# OpenBook_v13.net
KiCad netlist of a schematic drawn in EAGLE
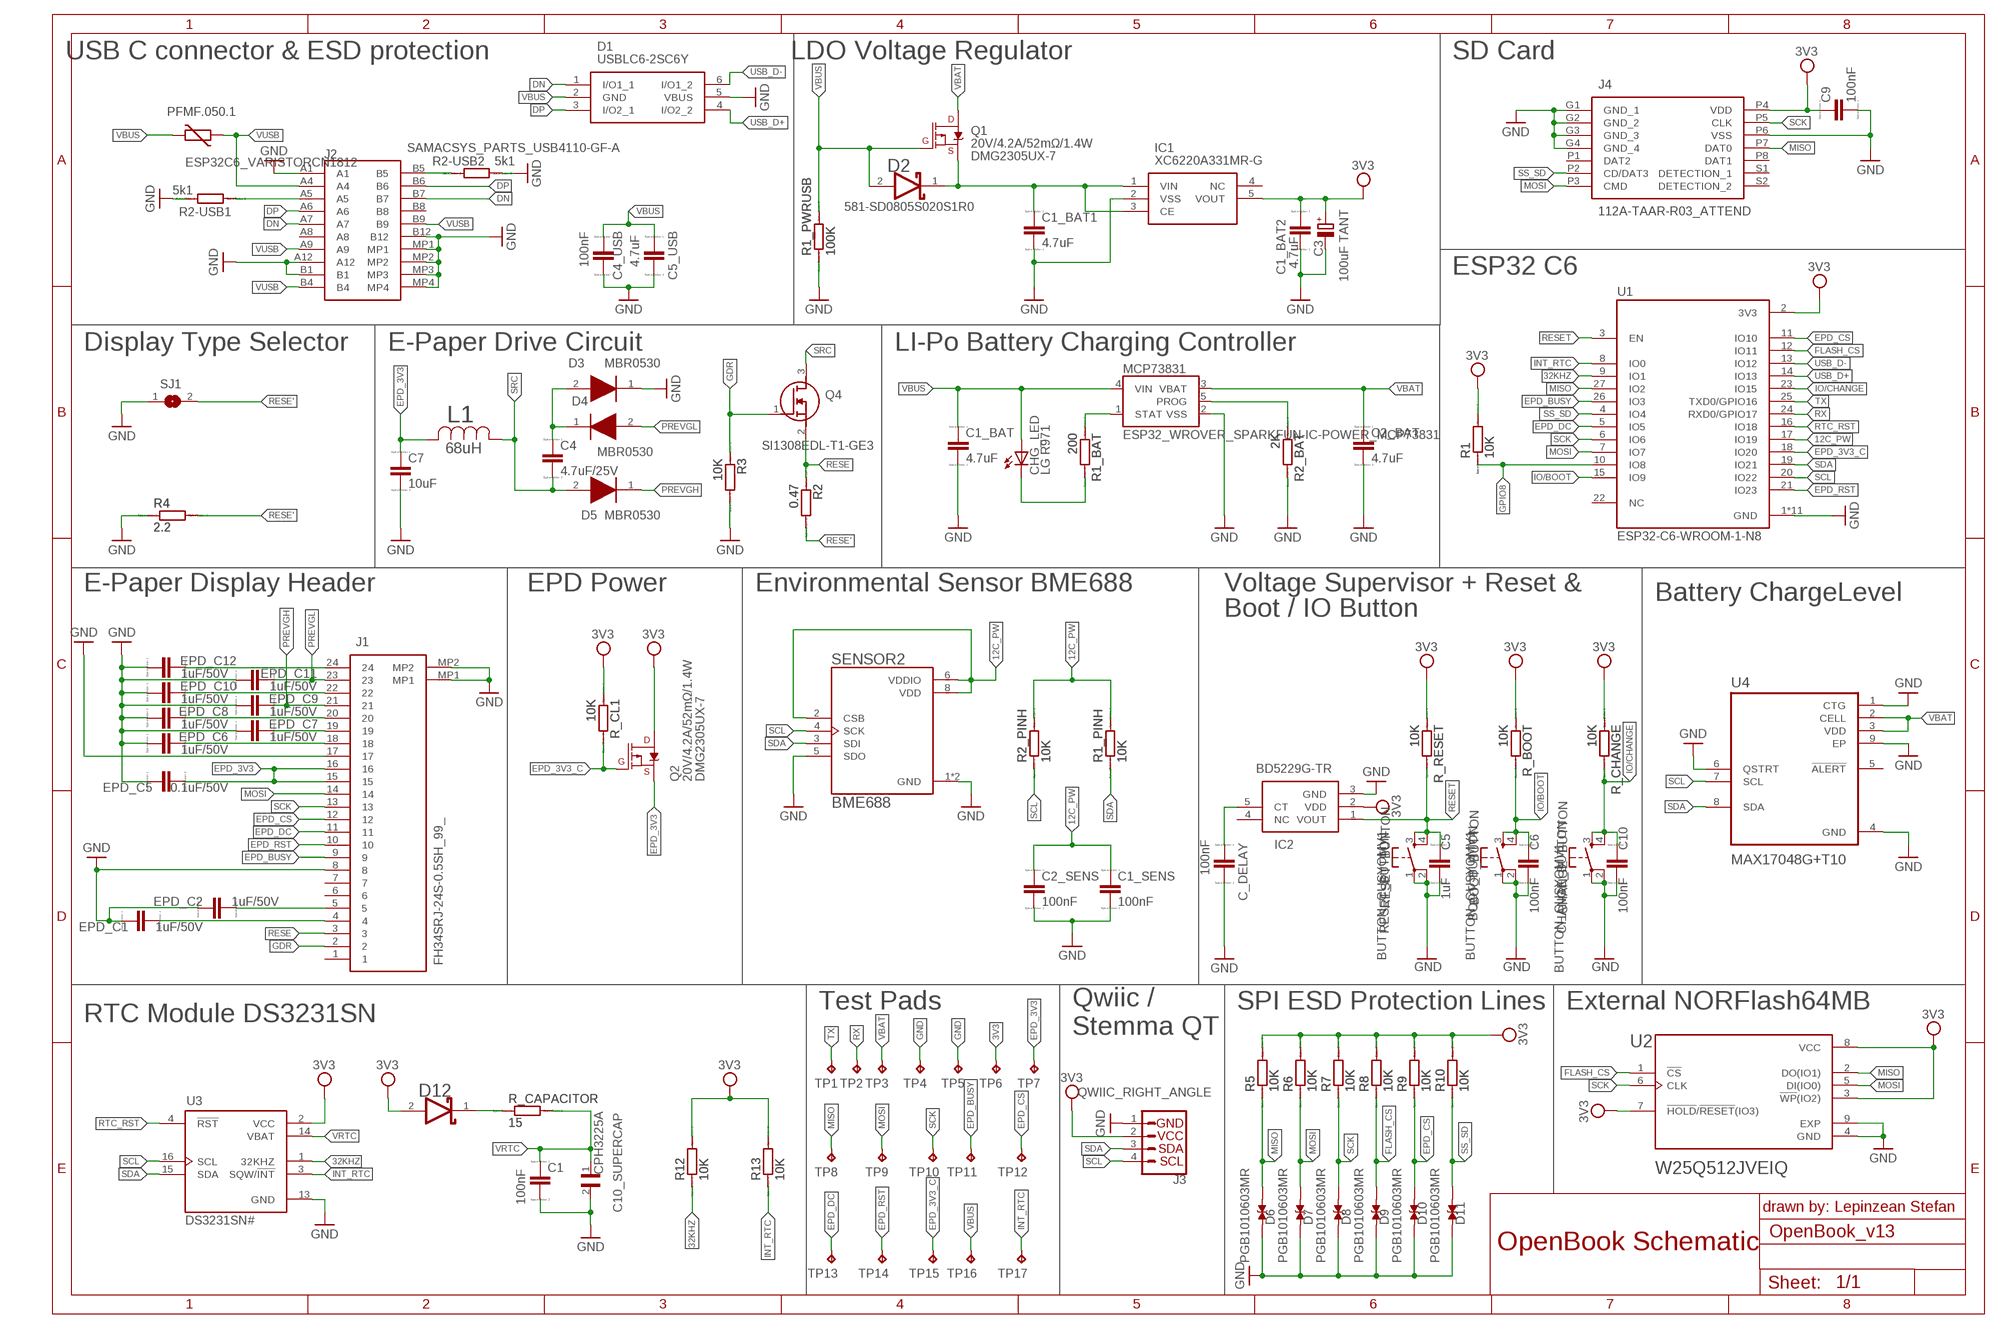
[diagram p0: schematic, sheet 1]

(export (version "E")
  (design (tool "Eeschema 10.0.6"))
  (components
    (comp (ref "BOOT_BUTTON")
      (value "BUTTON_CUSYOMV1")
      (footprint "eagle-import:MYBUTTON")
      (libsource (lib "eagle-import") (part "BUTTON_CUSYOMV1"))
    )
    (comp (ref "C1")
      (value "100nF")
      (footprint "eagle-import:EAGLE-LTSPICE_C0402")
      (libsource (lib "eagle-import") (part "EAGLE-LTSPICE_CC0402"))
    )
    (comp (ref "C1_BAT")
      (value "4.7uF")
      (footprint "eagle-import:EAGLE-LTSPICE_C0402")
      (libsource (lib "eagle-import") (part "EAGLE-LTSPICE_CC0402"))
    )
    (comp (ref "C1_BAT1")
      (value "4.7uF")
      (footprint "eagle-import:EAGLE-LTSPICE_C0402")
      (libsource (lib "eagle-import") (part "EAGLE-LTSPICE_CC0402"))
    )
    (comp (ref "C1_BAT2")
      (value "4.7uF")
      (footprint "eagle-import:EAGLE-LTSPICE_C0402")
      (libsource (lib "eagle-import") (part "EAGLE-LTSPICE_CC0402"))
    )
    (comp (ref "C1_SENS")
      (value "100nF")
      (footprint "eagle-import:EAGLE-LTSPICE_C0402")
      (libsource (lib "eagle-import") (part "EAGLE-LTSPICE_CC0402"))
    )
    (comp (ref "C2_BAT")
      (value "4.7uF")
      (footprint "eagle-import:EAGLE-LTSPICE_C0402")
      (libsource (lib "eagle-import") (part "EAGLE-LTSPICE_CC0402"))
    )
    (comp (ref "C2_SENS")
      (value "100nF")
      (footprint "eagle-import:EAGLE-LTSPICE_C0402")
      (libsource (lib "eagle-import") (part "EAGLE-LTSPICE_CC0402"))
    )
    (comp (ref "C3")
      (value "100uF TANT")
      (footprint "eagle-import:RCL_CT3528")
      (libsource (lib "eagle-import") (part "RCL_CPOL-EUCT3528"))
    )
    (comp (ref "C4")
      (value "4.7uF/25V")
      (footprint "eagle-import:EAGLE-LTSPICE_C0402")
      (libsource (lib "eagle-import") (part "EAGLE-LTSPICE_CC0402"))
    )
    (comp (ref "C4_USB")
      (value "100nF")
      (footprint "eagle-import:EAGLE-LTSPICE_C0402")
      (libsource (lib "eagle-import") (part "EAGLE-LTSPICE_CC0402"))
    )
    (comp (ref "C5")
      (value "1uF")
      (footprint "eagle-import:EAGLE-LTSPICE_C0402")
      (libsource (lib "eagle-import") (part "EAGLE-LTSPICE_CC0402"))
    )
    (comp (ref "C5_USB")
      (value "4.7uF")
      (footprint "eagle-import:EAGLE-LTSPICE_C0402")
      (libsource (lib "eagle-import") (part "EAGLE-LTSPICE_CC0402"))
    )
    (comp (ref "C6")
      (value "100nF")
      (footprint "eagle-import:EAGLE-LTSPICE_C0402")
      (libsource (lib "eagle-import") (part "EAGLE-LTSPICE_CC0402"))
    )
    (comp (ref "C7")
      (value "10uF")
      (footprint "eagle-import:EAGLE-LTSPICE_C0402")
      (libsource (lib "eagle-import") (part "EAGLE-LTSPICE_CC0402"))
    )
    (comp (ref "C9")
      (value "100nF")
      (footprint "eagle-import:EAGLE-LTSPICE_C0402")
      (libsource (lib "eagle-import") (part "EAGLE-LTSPICE_CC0402"))
    )
    (comp (ref "C10")
      (value "100nF")
      (footprint "eagle-import:EAGLE-LTSPICE_C0402")
      (libsource (lib "eagle-import") (part "EAGLE-LTSPICE_CC0402"))
    )
    (comp (ref "C10_SUPERCAP")
      (value "CPH3225A")
      (footprint "eagle-import:CAPCP3225X100N")
      (fields (field (name "MF") "Seiko Instruments"))
      (libsource (lib "eagle-import") (part "CPH3225A"))
    )
    (comp (ref "CHANGE_BUTTON")
      (value "BUTTON_CUSYOMV1")
      (footprint "eagle-import:MYBUTTON")
      (libsource (lib "eagle-import") (part "BUTTON_CUSYOMV1"))
    )
    (comp (ref "CHG_LED")
      (value "LG R971")
      (footprint "eagle-import:ADAFRUIT_CHIP-LED0603")
      (libsource (lib "eagle-import") (part "ADAFRUIT_LEDCHIP-LED0603"))
    )
    (comp (ref "C_DELAY")
      (value "100nF")
      (footprint "eagle-import:EAGLE-LTSPICE_C0402")
      (libsource (lib "eagle-import") (part "EAGLE-LTSPICE_CC0402"))
    )
    (comp (ref "D1")
      (value "USBLC6-2SC6Y")
      (footprint "eagle-import:SOT95P280X145-6N")
      (fields (field (name "MF") "STMicroelectronics"))
      (libsource (lib "eagle-import") (part "USBLC6-2SC6Y"))
    )
    (comp (ref "D2")
      (value "ESP32_WROVER_AVX---SD0805S020S1R0_AVX_SD0805S020S1R0_0_0AVX_SD0805S020S1R0_0_0")
      (footprint "eagle-import:ESP32_WROVER_AVX---SD0805S020S1R0_AVX_SD0805S020S1R0_0")
      (fields
        (field (name "DIGIKEY_PART_NUMBER") "478-7800-1-ND")
        (field (name "MF") "AVX")
        (field (name "MOUSER_PART_NUMBER") "581-SD0805S020S1R0")
      )
      (libsource (lib "eagle-import") (part "ESP32_WROVER_AVX---SD0805S020S1R0_AVX_SD0805S020S1R0_0_0AVX_SD0805S020S1R0_0_0"))
    )
    (comp (ref "D3")
      (value "MBR0530")
      (footprint "eagle-import:SOD3716X135N")
      (fields (field (name "MF") "ON Semiconductor"))
      (libsource (lib "eagle-import") (part "MBR0530"))
    )
    (comp (ref "D4")
      (value "MBR0530")
      (footprint "eagle-import:SOD3716X135N")
      (fields (field (name "MF") "ON Semiconductor"))
      (libsource (lib "eagle-import") (part "MBR0530"))
    )
    (comp (ref "D5")
      (value "MBR0530")
      (footprint "eagle-import:SOD3716X135N")
      (fields (field (name "MF") "ON Semiconductor"))
      (libsource (lib "eagle-import") (part "MBR0530"))
    )
    (comp (ref "D6")
      (value "PGB1010603MR")
      (footprint "eagle-import:DIOC1608X36N")
      (fields (field (name "MF") "Littelfuse Inc."))
      (libsource (lib "eagle-import") (part "PGB1010603MR"))
    )
    (comp (ref "D7")
      (value "PGB1010603MR")
      (footprint "eagle-import:DIOC1608X36N")
      (fields (field (name "MF") "Littelfuse Inc."))
      (libsource (lib "eagle-import") (part "PGB1010603MR"))
    )
    (comp (ref "D8")
      (value "PGB1010603MR")
      (footprint "eagle-import:DIOC1608X36N")
      (fields (field (name "MF") "Littelfuse Inc."))
      (libsource (lib "eagle-import") (part "PGB1010603MR"))
    )
    (comp (ref "D9")
      (value "PGB1010603MR")
      (footprint "eagle-import:DIOC1608X36N")
      (fields (field (name "MF") "Littelfuse Inc."))
      (libsource (lib "eagle-import") (part "PGB1010603MR"))
    )
    (comp (ref "D10")
      (value "PGB1010603MR")
      (footprint "eagle-import:DIOC1608X36N")
      (fields (field (name "MF") "Littelfuse Inc."))
      (libsource (lib "eagle-import") (part "PGB1010603MR"))
    )
    (comp (ref "D11")
      (value "PGB1010603MR")
      (footprint "eagle-import:DIOC1608X36N")
      (fields (field (name "MF") "Littelfuse Inc."))
      (libsource (lib "eagle-import") (part "PGB1010603MR"))
    )
    (comp (ref "D12")
      (value "ESP32_WROVER_AVX---SD0805S020S1R0_AVX_SD0805S020S1R0_0_0AVX_SD0805S020S1R0_0_0")
      (footprint "eagle-import:ESP32_WROVER_AVX---SD0805S020S1R0_AVX_SD0805S020S1R0_0")
      (fields
        (field (name "DIGIKEY_PART_NUMBER") "478-7800-1-ND")
        (field (name "MF") "AVX")
        (field (name "MOUSER_PART_NUMBER") "581-SD0805S020S1R0")
      )
      (libsource (lib "eagle-import") (part "ESP32_WROVER_AVX---SD0805S020S1R0_AVX_SD0805S020S1R0_0_0AVX_SD0805S020S1R0_0_0"))
    )
    (comp (ref "EPD_C1")
      (value "1uF/50V")
      (footprint "eagle-import:EAGLE-LTSPICE_C0402")
      (libsource (lib "eagle-import") (part "EAGLE-LTSPICE_CC0402"))
    )
    (comp (ref "EPD_C2")
      (value "1uF/50V")
      (footprint "eagle-import:EAGLE-LTSPICE_C0402")
      (libsource (lib "eagle-import") (part "EAGLE-LTSPICE_CC0402"))
    )
    (comp (ref "EPD_C5")
      (value "0.1uF/50V")
      (footprint "eagle-import:EAGLE-LTSPICE_C0402")
      (libsource (lib "eagle-import") (part "EAGLE-LTSPICE_CC0402"))
    )
    (comp (ref "EPD_C6")
      (value "1uF/50V")
      (footprint "eagle-import:EAGLE-LTSPICE_C0402")
      (libsource (lib "eagle-import") (part "EAGLE-LTSPICE_CC0402"))
    )
    (comp (ref "EPD_C7")
      (value "1uF/50V")
      (footprint "eagle-import:EAGLE-LTSPICE_C0402")
      (libsource (lib "eagle-import") (part "EAGLE-LTSPICE_CC0402"))
    )
    (comp (ref "EPD_C8")
      (value "1uF/50V")
      (footprint "eagle-import:EAGLE-LTSPICE_C0402")
      (libsource (lib "eagle-import") (part "EAGLE-LTSPICE_CC0402"))
    )
    (comp (ref "EPD_C9")
      (value "1uF/50V")
      (footprint "eagle-import:EAGLE-LTSPICE_C0402")
      (libsource (lib "eagle-import") (part "EAGLE-LTSPICE_CC0402"))
    )
    (comp (ref "EPD_C10")
      (value "1uF/50V")
      (footprint "eagle-import:EAGLE-LTSPICE_C0402")
      (libsource (lib "eagle-import") (part "EAGLE-LTSPICE_CC0402"))
    )
    (comp (ref "EPD_C11")
      (value "1uF/50V")
      (footprint "eagle-import:EAGLE-LTSPICE_C0402")
      (libsource (lib "eagle-import") (part "EAGLE-LTSPICE_CC0402"))
    )
    (comp (ref "EPD_C12")
      (value "1uF/50V")
      (footprint "eagle-import:EAGLE-LTSPICE_C0402")
      (libsource (lib "eagle-import") (part "EAGLE-LTSPICE_CC0402"))
    )
    (comp (ref "IC1")
      (value "XC6220A331MR-G")
      (footprint "eagle-import:SOT95P280X120-5N")
      (fields (field (name "MOUSER_PART_NUMBER") "865-XC6220A331MR-G"))
      (libsource (lib "eagle-import") (part "XC6220A331MR-G"))
    )
    (comp (ref "IC2")
      (value "BD5229G-TR")
      (footprint "eagle-import:SOT95P280X125-5N")
      (fields (field (name "MOUSER_PART_NUMBER") "755-BD5229G-TR"))
      (libsource (lib "eagle-import") (part "BD5229G-TR"))
    )
    (comp (ref "J1")
      (value "FH34SRJ-24S-0.5SH_99_")
      (footprint "eagle-import:FH34SRJ24S05SH99")
      (fields
        (field (name "MANUFACTURER_PART_NUMBER") "FH34SRJ-24S-0.5SH(99)")
        (field (name "MOUSER_PART_NUMBER") "798-FH34SRJ24S05SH99")
      )
      (libsource (lib "eagle-import") (part "FH34SRJ-24S-0.5SH_99_"))
    )
    (comp (ref "J2")
      (value "SAMACSYS_PARTS_USB4110-GF-A")
      (footprint "eagle-import:SAMACSYS_PARTS_USB4110GFA")
      (fields
        (field (name "MANUFACTURER_PART_NUMBER") "USB4110-GF-A")
        (field (name "MOUSER_PART_NUMBER") "640-USB4110-GF-A")
      )
      (libsource (lib "eagle-import") (part "SAMACSYS_PARTS_USB4110-GF-A"))
    )
    (comp (ref "J3")
      (value "QWIIC_RIGHT_ANGLE")
      (footprint "eagle-import:JST04_1MM_RA")
      (libsource (lib "eagle-import") (part "QWIIC_CONNECTORJS-1MM"))
    )
    (comp (ref "J4")
      (value "112A-TAAR-R03_ATTEND")
      (footprint "eagle-import:112ATAARR03ATTEND")
      (fields (field (name "MANUFACTURER_PART_NUMBER") "112A-TAAR-R03 ATTEND"))
      (libsource (lib "eagle-import") (part "112A-TAAR-R03_ATTEND"))
    )
    (comp (ref "L1")
      (value "68uH")
      (footprint "eagle-import:IND_4828-WE-TPC_WRE")
      (fields
        (field (name "MANUFACTURER_PART_NUMBER") "744043680")
        (field (name "COPYRIGHT") "Copyright (C) 2024 Ultra Librarian. All rights reserved.")
      )
      (libsource (lib "eagle-import") (part "744043680IND_4828-WE-TPC_WRE"))
    )
    (comp (ref "MCP73831")
      (value "ESP32_WROVER_SPARKFUN-IC-POWER_MCP73831")
      (footprint "eagle-import:ESP32_WROVER_SPARKFUN-IC-POWER_SOT23-5")
      (libsource (lib "eagle-import") (part "ESP32_WROVER_SPARKFUN-IC-POWER_MCP73831"))
    )
    (comp (ref "PFMF.050.1")
      (value "ESP32C6_VARISTORCN1812")
      (footprint "eagle-import:ESP32C6_VARISTOR_CT_CN1812")
      (libsource (lib "eagle-import") (part "ESP32C6_VARISTORCN1812"))
    )
    (comp (ref "Q1")
      (value "20V/4.2A/52mΩ/1.4W")
      (footprint "eagle-import:ESP32_WROVER_SPARKFUN-DISCRETESEMI_SOT23-3")
      (fields (field (name "PROD_ID") "DMG2305UX-7"))
      (libsource (lib "eagle-import") (part "ESP32_WROVER_SPARKFUN-DISCRETESEMI_MOSFET_PCH-DMG2305UX-7"))
    )
    (comp (ref "Q2")
      (value "20V/4.2A/52mΩ/1.4W")
      (footprint "eagle-import:ESP32_WROVER_SPARKFUN-DISCRETESEMI_SOT23-3")
      (fields (field (name "PROD_ID") "DMG2305UX-7"))
      (libsource (lib "eagle-import") (part "ESP32_WROVER_SPARKFUN-DISCRETESEMI_MOSFET_PCH-DMG2305UX-7"))
    )
    (comp (ref "Q4")
      (value "SI1308EDL-T1-GE3")
      (footprint "eagle-import:SOT65P210X110-3N")
      (fields (field (name "MF") "Vishay Siliconix"))
      (libsource (lib "eagle-import") (part "SI1308EDL-T1-GE3"))
    )
    (comp (ref "R1")
      (value "10K")
      (footprint "eagle-import:R0402")
      (libsource (lib "eagle-import") (part "ESP32_WROVER_EAGLE-LTSPICE_RR0402"))
    )
    (comp (ref "R1_BAT")
      (value "200")
      (footprint "eagle-import:R0402")
      (libsource (lib "eagle-import") (part "ESP32_WROVER_EAGLE-LTSPICE_RR0402"))
    )
    (comp (ref "R1_PINH")
      (value "10K")
      (footprint "eagle-import:R0402")
      (libsource (lib "eagle-import") (part "ESP32_WROVER_EAGLE-LTSPICE_RR0402"))
    )
    (comp (ref "R1_PWRUSB")
      (value "100K")
      (footprint "eagle-import:R0402")
      (libsource (lib "eagle-import") (part "ESP32_WROVER_EAGLE-LTSPICE_RR0402"))
    )
    (comp (ref "R2")
      (value "0.47")
      (footprint "eagle-import:R0402")
      (libsource (lib "eagle-import") (part "ESP32_WROVER_EAGLE-LTSPICE_RR0402"))
    )
    (comp (ref "R2-USB1")
      (value "5k1")
      (footprint "eagle-import:R0402")
      (libsource (lib "eagle-import") (part "ESP32_WROVER_EAGLE-LTSPICE_RR0402"))
    )
    (comp (ref "R2-USB2")
      (value "5k1")
      (footprint "eagle-import:R0402")
      (libsource (lib "eagle-import") (part "ESP32_WROVER_EAGLE-LTSPICE_RR0402"))
    )
    (comp (ref "R2_BAT")
      (value "2K")
      (footprint "eagle-import:R0402")
      (libsource (lib "eagle-import") (part "ESP32_WROVER_EAGLE-LTSPICE_RR0402"))
    )
    (comp (ref "R2_PINH")
      (value "10K")
      (footprint "eagle-import:R0402")
      (libsource (lib "eagle-import") (part "ESP32_WROVER_EAGLE-LTSPICE_RR0402"))
    )
    (comp (ref "R3")
      (value "10K")
      (footprint "eagle-import:R0402")
      (libsource (lib "eagle-import") (part "ESP32_WROVER_EAGLE-LTSPICE_RR0402"))
    )
    (comp (ref "R4")
      (value "2.2")
      (footprint "eagle-import:R0402")
      (libsource (lib "eagle-import") (part "ESP32_WROVER_EAGLE-LTSPICE_RR0402"))
    )
    (comp (ref "R5")
      (value "10K")
      (footprint "eagle-import:R0402")
      (libsource (lib "eagle-import") (part "ESP32_WROVER_EAGLE-LTSPICE_RR0402"))
    )
    (comp (ref "R6")
      (value "10K")
      (footprint "eagle-import:R0402")
      (libsource (lib "eagle-import") (part "ESP32_WROVER_EAGLE-LTSPICE_RR0402"))
    )
    (comp (ref "R7")
      (value "10K")
      (footprint "eagle-import:R0402")
      (libsource (lib "eagle-import") (part "ESP32_WROVER_EAGLE-LTSPICE_RR0402"))
    )
    (comp (ref "R8")
      (value "10K")
      (footprint "eagle-import:R0402")
      (libsource (lib "eagle-import") (part "ESP32_WROVER_EAGLE-LTSPICE_RR0402"))
    )
    (comp (ref "R9")
      (value "10K")
      (footprint "eagle-import:R0402")
      (libsource (lib "eagle-import") (part "ESP32_WROVER_EAGLE-LTSPICE_RR0402"))
    )
    (comp (ref "R10")
      (value "10K")
      (footprint "eagle-import:R0402")
      (libsource (lib "eagle-import") (part "ESP32_WROVER_EAGLE-LTSPICE_RR0402"))
    )
    (comp (ref "R12")
      (value "10K")
      (footprint "eagle-import:R0402")
      (libsource (lib "eagle-import") (part "ESP32_WROVER_EAGLE-LTSPICE_RR0402"))
    )
    (comp (ref "R13")
      (value "10K")
      (footprint "eagle-import:R0402")
      (libsource (lib "eagle-import") (part "ESP32_WROVER_EAGLE-LTSPICE_RR0402"))
    )
    (comp (ref "RESET_BUTTON")
      (value "BUTTON_CUSYOMV1")
      (footprint "eagle-import:MYBUTTON")
      (libsource (lib "eagle-import") (part "BUTTON_CUSYOMV1"))
    )
    (comp (ref "R_BOOT")
      (value "10K")
      (footprint "eagle-import:R0402")
      (libsource (lib "eagle-import") (part "ESP32_WROVER_EAGLE-LTSPICE_RR0402"))
    )
    (comp (ref "R_CAPACITOR")
      (value "15")
      (footprint "eagle-import:R0402")
      (libsource (lib "eagle-import") (part "ESP32_WROVER_EAGLE-LTSPICE_RR0402"))
    )
    (comp (ref "R_CHANGE")
      (value "10K")
      (footprint "eagle-import:R0402")
      (libsource (lib "eagle-import") (part "ESP32_WROVER_EAGLE-LTSPICE_RR0402"))
    )
    (comp (ref "R_CL1")
      (value "10K")
      (footprint "eagle-import:R0402")
      (libsource (lib "eagle-import") (part "ESP32_WROVER_EAGLE-LTSPICE_RR0402"))
    )
    (comp (ref "R_RESET")
      (value "10K")
      (footprint "eagle-import:R0402")
      (libsource (lib "eagle-import") (part "ESP32_WROVER_EAGLE-LTSPICE_RR0402"))
    )
    (comp (ref "SENSOR2")
      (value "BME688")
      (footprint "eagle-import:ESP32_WROVER_BME680_PSON80P300X300X100-8N")
      (fields (field (name "MF") "Bosch Sensortec") (field (name "MP") "BME680"))
      (libsource (lib "eagle-import") (part "ESP32_WROVER_BME680_BME680"))
    )
    (comp (ref "SJ1") (value "SJ") (footprint "eagle-import:SJ") (libsource (lib "eagle-import") (part "SJ")))
    (comp (ref "TP1")
      (value "TPTP20R")
      (footprint "eagle-import:TP20R")
      (libsource (lib "eagle-import") (part "TPTP20R"))
    )
    (comp (ref "TP2")
      (value "TPTP20R")
      (footprint "eagle-import:TP20R")
      (libsource (lib "eagle-import") (part "TPTP20R"))
    )
    (comp (ref "TP3")
      (value "TPTP20R")
      (footprint "eagle-import:TP20R")
      (libsource (lib "eagle-import") (part "TPTP20R"))
    )
    (comp (ref "TP4")
      (value "TPTP20R")
      (footprint "eagle-import:TP20R")
      (libsource (lib "eagle-import") (part "TPTP20R"))
    )
    (comp (ref "TP5")
      (value "TPTP20R")
      (footprint "eagle-import:TP20R")
      (libsource (lib "eagle-import") (part "TPTP20R"))
    )
    (comp (ref "TP6")
      (value "TPTP20R")
      (footprint "eagle-import:TP20R")
      (libsource (lib "eagle-import") (part "TPTP20R"))
    )
    (comp (ref "TP7")
      (value "TPTP20R")
      (footprint "eagle-import:TP20R")
      (libsource (lib "eagle-import") (part "TPTP20R"))
    )
    (comp (ref "TP8")
      (value "TPTP20R")
      (footprint "eagle-import:TP20R")
      (libsource (lib "eagle-import") (part "TPTP20R"))
    )
    (comp (ref "TP9")
      (value "TPTP20R")
      (footprint "eagle-import:TP20R")
      (libsource (lib "eagle-import") (part "TPTP20R"))
    )
    (comp (ref "TP10")
      (value "TPTP20R")
      (footprint "eagle-import:TP20R")
      (libsource (lib "eagle-import") (part "TPTP20R"))
    )
    (comp (ref "TP11")
      (value "TPTP20R")
      (footprint "eagle-import:TP20R")
      (libsource (lib "eagle-import") (part "TPTP20R"))
    )
    (comp (ref "TP12")
      (value "TPTP20R")
      (footprint "eagle-import:TP20R")
      (libsource (lib "eagle-import") (part "TPTP20R"))
    )
    (comp (ref "TP13")
      (value "TPTP20R")
      (footprint "eagle-import:TP20R")
      (libsource (lib "eagle-import") (part "TPTP20R"))
    )
    (comp (ref "TP14")
      (value "TPTP20R")
      (footprint "eagle-import:TP20R")
      (libsource (lib "eagle-import") (part "TPTP20R"))
    )
    (comp (ref "TP15")
      (value "TPTP20R")
      (footprint "eagle-import:TP20R")
      (libsource (lib "eagle-import") (part "TPTP20R"))
    )
    (comp (ref "TP16")
      (value "TPTP20R")
      (footprint "eagle-import:TP20R")
      (libsource (lib "eagle-import") (part "TPTP20R"))
    )
    (comp (ref "TP17")
      (value "TPTP20R")
      (footprint "eagle-import:TP20R")
      (libsource (lib "eagle-import") (part "TPTP20R"))
    )
    (comp (ref "U1")
      (value "ESP32-C6-WROOM-1-N8")
      (footprint "eagle-import:XCVR_ESP32-C6-WROOM-1-N8")
      (fields (field (name "MF") "Espressif Systems"))
      (libsource (lib "eagle-import") (part "ESP32-C6-WROOM-1-N8"))
    )
    (comp (ref "U2")
      (value "W25Q512JVEIQ")
      (footprint "eagle-import:SON127P600X800X80-9N")
      (fields (field (name "MF") "Winbond Electronics"))
      (libsource (lib "eagle-import") (part "W25Q512JVEIQ"))
    )
    (comp (ref "U3")
      (value "DS3231SN#")
      (footprint "eagle-import:SOIC127P1032X265-16N")
      (fields (field (name "MF") "Analog Devices"))
      (libsource (lib "eagle-import") (part "DS3231SN#"))
    )
    (comp (ref "U4")
      (value "MAX17048G+T10")
      (footprint "eagle-import:SON50P200X200X80-9N")
      (fields (field (name "MF") "Analog Devices"))
      (libsource (lib "eagle-import") (part "MAX17048G+T10"))
    )
  )
  (nets
    (net (code "1") (name "3V3") (class "Default")
      (node (ref "C1_BAT2") (pin "2") (pinfunction "2_2") (pintype "passive"))
      (node (ref "C3") (pin "+") (pinfunction "+_+") (pintype "passive"))
      (node (ref "C9") (pin "1") (pinfunction "1_1") (pintype "passive"))
      (node (ref "D12") (pin "2") (pinfunction "ANODE_2") (pintype "bidirectional"))
      (node (ref "IC1") (pin "5") (pinfunction "VOUT_5") (pintype "bidirectional"))
      (node (ref "IC2") (pin "2") (pinfunction "VDD_2") (pintype "bidirectional"))
      (node (ref "J3") (pin "2") (pinfunction "2_2") (pintype "power_in"))
      (node (ref "J4") (pin "P4") (pinfunction "VDD_P4") (pintype "bidirectional"))
      (node (ref "Q2") (pin "3") (pinfunction "D_3") (pintype "bidirectional"))
      (node (ref "R1") (pin "2") (pinfunction "2_2") (pintype "passive"))
      (node (ref "R10") (pin "2") (pinfunction "2_2") (pintype "passive"))
      (node (ref "R12") (pin "2") (pinfunction "2_2") (pintype "passive"))
      (node (ref "R13") (pin "2") (pinfunction "2_2") (pintype "passive"))
      (node (ref "R5") (pin "2") (pinfunction "2_2") (pintype "passive"))
      (node (ref "R6") (pin "2") (pinfunction "2_2") (pintype "passive"))
      (node (ref "R7") (pin "2") (pinfunction "2_2") (pintype "passive"))
      (node (ref "R8") (pin "2") (pinfunction "2_2") (pintype "passive"))
      (node (ref "R9") (pin "2") (pinfunction "2_2") (pintype "passive"))
      (node (ref "R_BOOT") (pin "1") (pinfunction "1_1") (pintype "passive"))
      (node (ref "R_CHANGE") (pin "1") (pinfunction "1_1") (pintype "passive"))
      (node (ref "R_CL1") (pin "1") (pinfunction "1_1") (pintype "passive"))
      (node (ref "R_RESET") (pin "1") (pinfunction "1_1") (pintype "passive"))
      (node (ref "TP6") (pin "TP") (pinfunction "TP_TP") (pintype "input"))
      (node (ref "U1") (pin "2") (pinfunction "3V3_2") (pintype "power_in"))
      (node (ref "U2") (pin "3") (pinfunction "~{WP}(IO2)_3") (pintype "bidirectional"))
      (node (ref "U2") (pin "7") (pinfunction "~{HOLD}/~{RESET}(IO3)_7") (pintype "bidirectional"))
      (node (ref "U2") (pin "8") (pinfunction "VCC_8") (pintype "power_in"))
      (node (ref "U3") (pin "2") (pinfunction "VCC_2") (pintype "power_in"))
    )
    (net (code "2") (name "12C_PW") (class "Default")
      (node (ref "C1_SENS") (pin "1") (pinfunction "1_1") (pintype "passive"))
      (node (ref "C2_SENS") (pin "1") (pinfunction "1_1") (pintype "passive"))
      (node (ref "R1_PINH") (pin "2") (pinfunction "2_2") (pintype "passive"))
      (node (ref "R2_PINH") (pin "2") (pinfunction "2_2") (pintype "passive"))
      (node (ref "SENSOR2") (pin "2") (pinfunction "CSB_2") (pintype "input"))
      (node (ref "SENSOR2") (pin "6") (pinfunction "VDDIO_6") (pintype "power_in"))
      (node (ref "SENSOR2") (pin "8") (pinfunction "VDD_8") (pintype "power_in"))
      (node (ref "U1") (pin "17") (pinfunction "IO19_17") (pintype "bidirectional"))
    )
    (net (code "3") (name "32KHZ") (class "Default")
      (node (ref "R12") (pin "1") (pinfunction "1_1") (pintype "passive"))
      (node (ref "U1") (pin "9") (pinfunction "IO1_9") (pintype "bidirectional"))
      (node (ref "U3") (pin "1") (pinfunction "32KHZ_1") (pintype "output"))
    )
    (net (code "4") (name "DN") (class "Default")
      (node (ref "D1") (pin "1") (pinfunction "I/O1_1_1") (pintype "bidirectional"))
      (node (ref "J2") (pin "A7") (pinfunction "A7_A7") (pintype "bidirectional"))
      (node (ref "J2") (pin "B7") (pinfunction "B7_B7") (pintype "bidirectional"))
    )
    (net (code "5") (name "DP") (class "Default")
      (node (ref "D1") (pin "3") (pinfunction "I/O2_1_3") (pintype "bidirectional"))
      (node (ref "J2") (pin "A6") (pinfunction "A6_A6") (pintype "bidirectional"))
      (node (ref "J2") (pin "B6") (pinfunction "B6_B6") (pintype "bidirectional"))
    )
    (net (code "6") (name "EPD_3V3") (class "Default")
      (node (ref "C7") (pin "1") (pinfunction "1_1") (pintype "passive"))
      (node (ref "EPD_C5") (pin "2") (pinfunction "2_2") (pintype "passive"))
      (node (ref "J1") (pin "15") (pinfunction "15_15") (pintype "bidirectional"))
      (node (ref "J1") (pin "16") (pinfunction "16_16") (pintype "bidirectional"))
      (node (ref "L1") (pin "2") (pinfunction "2_2") (pintype "passive"))
      (node (ref "Q2") (pin "2") (pinfunction "S_2") (pintype "bidirectional"))
      (node (ref "TP7") (pin "TP") (pinfunction "TP_TP") (pintype "input"))
    )
    (net (code "7") (name "EPD_3V3_C") (class "Default")
      (node (ref "Q2") (pin "1") (pinfunction "G_1") (pintype "bidirectional"))
      (node (ref "R_CL1") (pin "2") (pinfunction "2_2") (pintype "passive"))
      (node (ref "TP15") (pin "TP") (pinfunction "TP_TP") (pintype "input"))
      (node (ref "U1") (pin "18") (pinfunction "IO20_18") (pintype "bidirectional"))
    )
    (net (code "8") (name "EPD_BUSY") (class "Default")
      (node (ref "J1") (pin "9") (pinfunction "9_9") (pintype "bidirectional"))
      (node (ref "TP11") (pin "TP") (pinfunction "TP_TP") (pintype "input"))
      (node (ref "U1") (pin "26") (pinfunction "IO3_26") (pintype "bidirectional"))
    )
    (net (code "9") (name "EPD_CS") (class "Default")
      (node (ref "D10") (pin "2") (pinfunction "2_2") (pintype "passive"))
      (node (ref "J1") (pin "12") (pinfunction "12_12") (pintype "bidirectional"))
      (node (ref "R9") (pin "1") (pinfunction "1_1") (pintype "passive"))
      (node (ref "TP12") (pin "TP") (pinfunction "TP_TP") (pintype "input"))
      (node (ref "U1") (pin "11") (pinfunction "IO10_11") (pintype "bidirectional"))
    )
    (net (code "10") (name "EPD_DC") (class "Default")
      (node (ref "J1") (pin "11") (pinfunction "11_11") (pintype "bidirectional"))
      (node (ref "TP13") (pin "TP") (pinfunction "TP_TP") (pintype "input"))
      (node (ref "U1") (pin "5") (pinfunction "IO5_5") (pintype "bidirectional"))
    )
    (net (code "11") (name "EPD_RST") (class "Default")
      (node (ref "J1") (pin "10") (pinfunction "10_10") (pintype "bidirectional"))
      (node (ref "TP14") (pin "TP") (pinfunction "TP_TP") (pintype "input"))
      (node (ref "U1") (pin "21") (pinfunction "IO23_21") (pintype "bidirectional"))
    )
    (net (code "12") (name "FLASH_CS") (class "Default")
      (node (ref "D9") (pin "2") (pinfunction "2_2") (pintype "passive"))
      (node (ref "R8") (pin "1") (pinfunction "1_1") (pintype "passive"))
      (node (ref "U1") (pin "12") (pinfunction "IO11_12") (pintype "bidirectional"))
      (node (ref "U2") (pin "1") (pinfunction "~{CS}_1") (pintype "input"))
    )
    (net (code "13") (name "GDR") (class "Default")
      (node (ref "J1") (pin "2") (pinfunction "2_2") (pintype "bidirectional"))
      (node (ref "Q4") (pin "1") (pinfunction "G_1") (pintype "bidirectional"))
      (node (ref "R3") (pin "1") (pinfunction "1_1") (pintype "passive"))
    )
    (net (code "14") (name "GND") (class "Default")
      (node (ref "BOOT_BUTTON") (pin "1") (pinfunction "1_1") (pintype "passive"))
      (node (ref "BOOT_BUTTON") (pin "2") (pinfunction "2_2") (pintype "passive"))
      (node (ref "C1") (pin "2") (pinfunction "2_2") (pintype "passive"))
      (node (ref "C10") (pin "2") (pinfunction "2_2") (pintype "passive"))
      (node (ref "C10_SUPERCAP") (pin "2") (pinfunction "2_2") (pintype "passive"))
      (node (ref "C1_BAT") (pin "2") (pinfunction "2_2") (pintype "passive"))
      (node (ref "C1_BAT1") (pin "2") (pinfunction "2_2") (pintype "passive"))
      (node (ref "C1_BAT2") (pin "1") (pinfunction "1_1") (pintype "passive"))
      (node (ref "C1_SENS") (pin "2") (pinfunction "2_2") (pintype "passive"))
      (node (ref "C2_BAT") (pin "2") (pinfunction "2_2") (pintype "passive"))
      (node (ref "C2_SENS") (pin "2") (pinfunction "2_2") (pintype "passive"))
      (node (ref "C3") (pin "-") (pinfunction "-_-") (pintype "passive"))
      (node (ref "C4_USB") (pin "2") (pinfunction "2_2") (pintype "passive"))
      (node (ref "C5") (pin "2") (pinfunction "2_2") (pintype "passive"))
      (node (ref "C5_USB") (pin "2") (pinfunction "2_2") (pintype "passive"))
      (node (ref "C6") (pin "2") (pinfunction "2_2") (pintype "passive"))
      (node (ref "C7") (pin "2") (pinfunction "2_2") (pintype "passive"))
      (node (ref "C9") (pin "2") (pinfunction "2_2") (pintype "passive"))
      (node (ref "CHANGE_BUTTON") (pin "1") (pinfunction "1_1") (pintype "passive"))
      (node (ref "CHANGE_BUTTON") (pin "2") (pinfunction "2_2") (pintype "passive"))
      (node (ref "C_DELAY") (pin "2") (pinfunction "2_2") (pintype "passive"))
      (node (ref "D1") (pin "5") (pinfunction "VBUS_5") (pintype "bidirectional"))
      (node (ref "D10") (pin "1") (pinfunction "1_1") (pintype "passive"))
      (node (ref "D11") (pin "1") (pinfunction "1_1") (pintype "passive"))
      (node (ref "D3") (pin "1") (pinfunction "K_1") (pintype "bidirectional"))
      (node (ref "D6") (pin "1") (pinfunction "1_1") (pintype "passive"))
      (node (ref "D7") (pin "1") (pinfunction "1_1") (pintype "passive"))
      (node (ref "D8") (pin "1") (pinfunction "1_1") (pintype "passive"))
      (node (ref "D9") (pin "1") (pinfunction "1_1") (pintype "passive"))
      (node (ref "EPD_C1") (pin "1") (pinfunction "1_1") (pintype "passive"))
      (node (ref "EPD_C10") (pin "1") (pinfunction "1_1") (pintype "passive"))
      (node (ref "EPD_C11") (pin "1") (pinfunction "1_1") (pintype "passive"))
      (node (ref "EPD_C12") (pin "1") (pinfunction "1_1") (pintype "passive"))
      (node (ref "EPD_C2") (pin "1") (pinfunction "1_1") (pintype "passive"))
      (node (ref "EPD_C5") (pin "1") (pinfunction "1_1") (pintype "passive"))
      (node (ref "EPD_C6") (pin "1") (pinfunction "1_1") (pintype "passive"))
      (node (ref "EPD_C7") (pin "1") (pinfunction "1_1") (pintype "passive"))
      (node (ref "EPD_C8") (pin "1") (pinfunction "1_1") (pintype "passive"))
      (node (ref "EPD_C9") (pin "1") (pinfunction "1_1") (pintype "passive"))
      (node (ref "IC1") (pin "2") (pinfunction "VSS_2") (pintype "bidirectional"))
      (node (ref "IC2") (pin "3") (pinfunction "GND_3") (pintype "bidirectional"))
      (node (ref "J1") (pin "17") (pinfunction "17_17") (pintype "bidirectional"))
      (node (ref "J1") (pin "8") (pinfunction "8_8") (pintype "bidirectional"))
      (node (ref "J1") (pin "MP1") (pinfunction "MP1_MP1") (pintype "bidirectional"))
      (node (ref "J1") (pin "MP2") (pinfunction "MP2_MP2") (pintype "bidirectional"))
      (node (ref "J2") (pin "A1") (pinfunction "A1_A1") (pintype "bidirectional"))
      (node (ref "J2") (pin "A12") (pinfunction "A12_A12") (pintype "bidirectional"))
      (node (ref "J2") (pin "B1") (pinfunction "B1_B1") (pintype "bidirectional"))
      (node (ref "J2") (pin "B12") (pinfunction "B12_B12") (pintype "bidirectional"))
      (node (ref "J2") (pin "MP1") (pinfunction "MP1_MP1") (pintype "bidirectional"))
      (node (ref "J2") (pin "MP2") (pinfunction "MP2_MP2") (pintype "bidirectional"))
      (node (ref "J2") (pin "MP3") (pinfunction "MP3_MP3") (pintype "bidirectional"))
      (node (ref "J2") (pin "MP4") (pinfunction "MP4_MP4") (pintype "bidirectional"))
      (node (ref "J3") (pin "1") (pinfunction "1_1") (pintype "power_in"))
      (node (ref "J4") (pin "G1") (pinfunction "GND_1_G1") (pintype "bidirectional"))
      (node (ref "J4") (pin "G2") (pinfunction "GND_2_G2") (pintype "bidirectional"))
      (node (ref "J4") (pin "G3") (pinfunction "GND_3_G3") (pintype "bidirectional"))
      (node (ref "J4") (pin "G4") (pinfunction "GND_4_G4") (pintype "bidirectional"))
      (node (ref "J4") (pin "P6") (pinfunction "VSS_P6") (pintype "bidirectional"))
      (node (ref "MCP73831") (pin "2") (pinfunction "VSS_2") (pintype "power_in"))
      (node (ref "R1_PWRUSB") (pin "1") (pinfunction "1_1") (pintype "passive"))
      (node (ref "R2-USB1") (pin "1") (pinfunction "1_1") (pintype "passive"))
      (node (ref "R2-USB2") (pin "2") (pinfunction "2_2") (pintype "passive"))
      (node (ref "R2_BAT") (pin "2") (pinfunction "2_2") (pintype "passive"))
      (node (ref "R3") (pin "2") (pinfunction "2_2") (pintype "passive"))
      (node (ref "R4") (pin "1") (pinfunction "1_1") (pintype "passive"))
      (node (ref "RESET_BUTTON") (pin "1") (pinfunction "1_1") (pintype "passive"))
      (node (ref "RESET_BUTTON") (pin "2") (pinfunction "2_2") (pintype "passive"))
      (node (ref "SENSOR2") (pin "1") (pinfunction "GND_1") (pintype "power_in"))
      (node (ref "SENSOR2") (pin "5") (pinfunction "SDO_5") (pintype "bidirectional"))
      (node (ref "SENSOR2") (pin "7") (pinfunction "GND_7") (pintype "power_in"))
      (node (ref "SJ1") (pin "1") (pinfunction "1_1") (pintype "passive"))
      (node (ref "TP4") (pin "TP") (pinfunction "TP_TP") (pintype "input"))
      (node (ref "TP5") (pin "TP") (pinfunction "TP_TP") (pintype "input"))
      (node (ref "U1") (pin "1") (pinfunction "GND_1") (pintype "power_in"))
      (node (ref "U1") (pin "28") (pinfunction "GND_28") (pintype "power_in"))
      (node (ref "U1") (pin "29_1") (pinfunction "GND_29_1") (pintype "power_in"))
      (node (ref "U1") (pin "29_2") (pinfunction "GND_29_2") (pintype "power_in"))
      (node (ref "U1") (pin "29_3") (pinfunction "GND_29_3") (pintype "power_in"))
      (node (ref "U1") (pin "29_4") (pinfunction "GND_29_4") (pintype "power_in"))
      (node (ref "U1") (pin "29_5") (pinfunction "GND_29_5") (pintype "power_in"))
      (node (ref "U1") (pin "29_6") (pinfunction "GND_29_6") (pintype "power_in"))
      (node (ref "U1") (pin "29_7") (pinfunction "GND_29_7") (pintype "power_in"))
      (node (ref "U1") (pin "29_8") (pinfunction "GND_29_8") (pintype "power_in"))
      (node (ref "U1") (pin "29_9") (pinfunction "GND_29_9") (pintype "power_in"))
      (node (ref "U2") (pin "4") (pinfunction "GND_4") (pintype "power_in"))
      (node (ref "U2") (pin "9") (pinfunction "EXP_9") (pintype "passive"))
      (node (ref "U3") (pin "13") (pinfunction "GND_13") (pintype "power_in"))
      (node (ref "U4") (pin "1") (pinfunction "CTG_1") (pintype "power_in"))
      (node (ref "U4") (pin "4") (pinfunction "GND_4") (pintype "power_in"))
      (node (ref "U4") (pin "6") (pinfunction "QSTRT_6") (pintype "input"))
      (node (ref "U4") (pin "9") (pinfunction "EP_9") (pintype "power_in"))
    )
    (net (code "15") (name "GPIO8") (class "Default")
      (node (ref "R1") (pin "1") (pinfunction "1_1") (pintype "passive"))
      (node (ref "U1") (pin "10") (pinfunction "IO8_10") (pintype "bidirectional"))
    )
    (net (code "16") (name "INT_RTC") (class "Default")
      (node (ref "R13") (pin "1") (pinfunction "1_1") (pintype "passive"))
      (node (ref "TP17") (pin "TP") (pinfunction "TP_TP") (pintype "input"))
      (node (ref "U1") (pin "8") (pinfunction "IO0_8") (pintype "bidirectional"))
      (node (ref "U3") (pin "3") (pinfunction "SQW/~{INT}_3") (pintype "output"))
    )
    (net (code "17") (name "IO{slash}BOOT") (class "Default")
      (node (ref "BOOT_BUTTON") (pin "3") (pinfunction "3_3") (pintype "passive"))
      (node (ref "BOOT_BUTTON") (pin "4") (pinfunction "4_4") (pintype "passive"))
      (node (ref "C6") (pin "1") (pinfunction "1_1") (pintype "passive"))
      (node (ref "R_BOOT") (pin "2") (pinfunction "2_2") (pintype "passive"))
      (node (ref "U1") (pin "15") (pinfunction "IO9_15") (pintype "bidirectional"))
    )
    (net (code "18") (name "IO{slash}CHANGE") (class "Default")
      (node (ref "C10") (pin "1") (pinfunction "1_1") (pintype "passive"))
      (node (ref "CHANGE_BUTTON") (pin "3") (pinfunction "3_3") (pintype "passive"))
      (node (ref "CHANGE_BUTTON") (pin "4") (pinfunction "4_4") (pintype "passive"))
      (node (ref "R_CHANGE") (pin "2") (pinfunction "2_2") (pintype "passive"))
      (node (ref "U1") (pin "23") (pinfunction "IO15_23") (pintype "bidirectional"))
    )
    (net (code "19") (name "MISO") (class "Default")
      (node (ref "D6") (pin "2") (pinfunction "2_2") (pintype "passive"))
      (node (ref "J4") (pin "P7") (pinfunction "DAT0_P7") (pintype "bidirectional"))
      (node (ref "R5") (pin "1") (pinfunction "1_1") (pintype "passive"))
      (node (ref "TP8") (pin "TP") (pinfunction "TP_TP") (pintype "input"))
      (node (ref "U1") (pin "27") (pinfunction "IO2_27") (pintype "bidirectional"))
      (node (ref "U2") (pin "2") (pinfunction "DO(IO1)_2") (pintype "bidirectional"))
    )
    (net (code "20") (name "MOSI") (class "Default")
      (node (ref "D7") (pin "2") (pinfunction "2_2") (pintype "passive"))
      (node (ref "J1") (pin "14") (pinfunction "14_14") (pintype "bidirectional"))
      (node (ref "J4") (pin "P3") (pinfunction "CMD_P3") (pintype "bidirectional"))
      (node (ref "R6") (pin "1") (pinfunction "1_1") (pintype "passive"))
      (node (ref "TP9") (pin "TP") (pinfunction "TP_TP") (pintype "input"))
      (node (ref "U1") (pin "7") (pinfunction "IO7_7") (pintype "bidirectional"))
      (node (ref "U2") (pin "5") (pinfunction "DI(IO0)_5") (pintype "bidirectional"))
    )
    (net (code "21") (name "Net-(CHG_LED-PadC)") (class "Default")
      (node (ref "CHG_LED") (pin "C") (pinfunction "C_C") (pintype "passive"))
      (node (ref "R1_BAT") (pin "2") (pinfunction "2_2") (pintype "passive"))
    )
    (net (code "22") (name "Net-(D2-CATHODE)") (class "Default")
      (node (ref "C1_BAT1") (pin "1") (pinfunction "1_1") (pintype "passive"))
      (node (ref "D2") (pin "1") (pinfunction "CATHODE_1") (pintype "bidirectional"))
      (node (ref "IC1") (pin "1") (pinfunction "VIN_1") (pintype "bidirectional"))
      (node (ref "IC1") (pin "3") (pinfunction "CE_3") (pintype "bidirectional"))
      (node (ref "Q1") (pin "2") (pinfunction "S_2") (pintype "bidirectional"))
    )
    (net (code "23") (name "Net-(D3-A)") (class "Default")
      (node (ref "C4") (pin "1") (pinfunction "1_1") (pintype "passive"))
      (node (ref "D3") (pin "2") (pinfunction "A_2") (pintype "bidirectional"))
      (node (ref "D4") (pin "1") (pinfunction "K_1") (pintype "bidirectional"))
    )
    (net (code "24") (name "Net-(D12-CATHODE)") (class "Default")
      (node (ref "D12") (pin "1") (pinfunction "CATHODE_1") (pintype "bidirectional"))
      (node (ref "R_CAPACITOR") (pin "1") (pinfunction "1_1") (pintype "passive"))
    )
    (net (code "25") (name "Net-(EPD_C1-Pad2)") (class "Default")
      (node (ref "EPD_C1") (pin "2") (pinfunction "2_2") (pintype "passive"))
      (node (ref "J1") (pin "4") (pinfunction "4_4") (pintype "bidirectional"))
    )
    (net (code "26") (name "Net-(EPD_C2-Pad2)") (class "Default")
      (node (ref "EPD_C2") (pin "2") (pinfunction "2_2") (pintype "passive"))
      (node (ref "J1") (pin "5") (pinfunction "5_5") (pintype "bidirectional"))
    )
    (net (code "27") (name "Net-(EPD_C6-Pad2)") (class "Default")
      (node (ref "EPD_C6") (pin "2") (pinfunction "2_2") (pintype "passive"))
      (node (ref "J1") (pin "18") (pinfunction "18_18") (pintype "bidirectional"))
    )
    (net (code "28") (name "Net-(EPD_C7-Pad2)") (class "Default")
      (node (ref "EPD_C7") (pin "2") (pinfunction "2_2") (pintype "passive"))
      (node (ref "J1") (pin "19") (pinfunction "19_19") (pintype "bidirectional"))
    )
    (net (code "29") (name "Net-(EPD_C8-Pad2)") (class "Default")
      (node (ref "EPD_C8") (pin "2") (pinfunction "2_2") (pintype "passive"))
      (node (ref "J1") (pin "20") (pinfunction "20_20") (pintype "bidirectional"))
    )
    (net (code "30") (name "Net-(EPD_C10-Pad2)") (class "Default")
      (node (ref "EPD_C10") (pin "2") (pinfunction "2_2") (pintype "passive"))
      (node (ref "J1") (pin "22") (pinfunction "22_22") (pintype "bidirectional"))
    )
    (net (code "31") (name "Net-(EPD_C12-Pad2)") (class "Default")
      (node (ref "EPD_C12") (pin "2") (pinfunction "2_2") (pintype "passive"))
      (node (ref "J1") (pin "24") (pinfunction "24_24") (pintype "bidirectional"))
    )
    (net (code "32") (name "Net-(IC2-CT)") (class "Default")
      (node (ref "C_DELAY") (pin "1") (pinfunction "1_1") (pintype "passive"))
      (node (ref "IC2") (pin "5") (pinfunction "CT_5") (pintype "bidirectional"))
    )
    (net (code "33") (name "Net-(J2-PadA5)") (class "Default")
      (node (ref "J2") (pin "A5") (pinfunction "A5_A5") (pintype "bidirectional"))
      (node (ref "R2-USB1") (pin "2") (pinfunction "2_2") (pintype "passive"))
    )
    (net (code "34") (name "Net-(J2-PadB5)") (class "Default")
      (node (ref "J2") (pin "B5") (pinfunction "B5_B5") (pintype "bidirectional"))
      (node (ref "R2-USB2") (pin "1") (pinfunction "1_1") (pintype "passive"))
    )
    (net (code "35") (name "Net-(MCP73831-PROG)") (class "Default")
      (node (ref "MCP73831") (pin "5") (pinfunction "PROG_5") (pintype "input"))
      (node (ref "R2_BAT") (pin "1") (pinfunction "1_1") (pintype "passive"))
    )
    (net (code "36") (name "Net-(MCP73831-STAT)") (class "Default")
      (node (ref "MCP73831") (pin "1") (pinfunction "STAT_1") (pintype "output"))
      (node (ref "R1_BAT") (pin "1") (pinfunction "1_1") (pintype "passive"))
    )
    (net (code "37") (name "PREVGH") (class "Default")
      (node (ref "D5") (pin "1") (pinfunction "K_1") (pintype "bidirectional"))
      (node (ref "EPD_C9") (pin "2") (pinfunction "2_2") (pintype "passive"))
      (node (ref "J1") (pin "21") (pinfunction "21_21") (pintype "bidirectional"))
    )
    (net (code "38") (name "PREVGL") (class "Default")
      (node (ref "D4") (pin "2") (pinfunction "A_2") (pintype "bidirectional"))
      (node (ref "EPD_C11") (pin "2") (pinfunction "2_2") (pintype "passive"))
      (node (ref "J1") (pin "23") (pinfunction "23_23") (pintype "bidirectional"))
    )
    (net (code "39") (name "RESE") (class "Default")
      (node (ref "J1") (pin "3") (pinfunction "3_3") (pintype "bidirectional"))
      (node (ref "Q4") (pin "2") (pinfunction "S_2") (pintype "bidirectional"))
      (node (ref "R2") (pin "1") (pinfunction "1_1") (pintype "passive"))
    )
    (net (code "40") (name "RESE'") (class "Default")
      (node (ref "R2") (pin "2") (pinfunction "2_2") (pintype "passive"))
      (node (ref "R4") (pin "2") (pinfunction "2_2") (pintype "passive"))
      (node (ref "SJ1") (pin "2") (pinfunction "2_2") (pintype "passive"))
    )
    (net (code "41") (name "RESET") (class "Default")
      (node (ref "C5") (pin "1") (pinfunction "1_1") (pintype "passive"))
      (node (ref "IC2") (pin "1") (pinfunction "VOUT_1") (pintype "bidirectional"))
      (node (ref "RESET_BUTTON") (pin "3") (pinfunction "3_3") (pintype "passive"))
      (node (ref "RESET_BUTTON") (pin "4") (pinfunction "4_4") (pintype "passive"))
      (node (ref "R_RESET") (pin "2") (pinfunction "2_2") (pintype "passive"))
      (node (ref "U1") (pin "3") (pinfunction "EN_3") (pintype "input"))
    )
    (net (code "42") (name "RTC_RST") (class "Default")
      (node (ref "U1") (pin "16") (pinfunction "IO18_16") (pintype "bidirectional"))
      (node (ref "U3") (pin "4") (pinfunction "~{RST}_4") (pintype "input"))
    )
    (net (code "43") (name "RX") (class "Default")
      (node (ref "TP2") (pin "TP") (pinfunction "TP_TP") (pintype "input"))
      (node (ref "U1") (pin "24") (pinfunction "RXD0/GPIO17_24") (pintype "bidirectional"))
    )
    (net (code "44") (name "SCK") (class "Default")
      (node (ref "D8") (pin "2") (pinfunction "2_2") (pintype "passive"))
      (node (ref "J1") (pin "13") (pinfunction "13_13") (pintype "bidirectional"))
      (node (ref "J4") (pin "P5") (pinfunction "CLK_P5") (pintype "bidirectional"))
      (node (ref "R7") (pin "1") (pinfunction "1_1") (pintype "passive"))
      (node (ref "TP10") (pin "TP") (pinfunction "TP_TP") (pintype "input"))
      (node (ref "U1") (pin "6") (pinfunction "IO6_6") (pintype "bidirectional"))
      (node (ref "U2") (pin "6") (pinfunction "CLK_6") (pintype "input"))
    )
    (net (code "45") (name "SCL") (class "Default")
      (node (ref "J3") (pin "4") (pinfunction "4_4") (pintype "passive"))
      (node (ref "R2_PINH") (pin "1") (pinfunction "1_1") (pintype "passive"))
      (node (ref "SENSOR2") (pin "4") (pinfunction "SCK_4") (pintype "input"))
      (node (ref "U1") (pin "20") (pinfunction "IO22_20") (pintype "bidirectional"))
      (node (ref "U3") (pin "16") (pinfunction "SCL_16") (pintype "input"))
      (node (ref "U4") (pin "7") (pinfunction "SCL_7") (pintype "input"))
    )
    (net (code "46") (name "SDA") (class "Default")
      (node (ref "J3") (pin "3") (pinfunction "3_3") (pintype "passive"))
      (node (ref "R1_PINH") (pin "1") (pinfunction "1_1") (pintype "passive"))
      (node (ref "SENSOR2") (pin "3") (pinfunction "SDI_3") (pintype "bidirectional"))
      (node (ref "U1") (pin "19") (pinfunction "IO21_19") (pintype "bidirectional"))
      (node (ref "U3") (pin "15") (pinfunction "SDA_15") (pintype "bidirectional"))
      (node (ref "U4") (pin "8") (pinfunction "SDA_8") (pintype "bidirectional"))
    )
    (net (code "47") (name "SRC") (class "Default")
      (node (ref "C4") (pin "2") (pinfunction "2_2") (pintype "passive"))
      (node (ref "D5") (pin "2") (pinfunction "A_2") (pintype "bidirectional"))
      (node (ref "L1") (pin "1") (pinfunction "1_1") (pintype "passive"))
      (node (ref "Q4") (pin "3") (pinfunction "D_3") (pintype "bidirectional"))
    )
    (net (code "48") (name "SS_SD") (class "Default")
      (node (ref "D11") (pin "2") (pinfunction "2_2") (pintype "passive"))
      (node (ref "J4") (pin "P2") (pinfunction "CD/DAT3_P2") (pintype "bidirectional"))
      (node (ref "R10") (pin "1") (pinfunction "1_1") (pintype "passive"))
      (node (ref "U1") (pin "4") (pinfunction "IO4_4") (pintype "bidirectional"))
    )
    (net (code "49") (name "TX") (class "Default")
      (node (ref "TP1") (pin "TP") (pinfunction "TP_TP") (pintype "input"))
      (node (ref "U1") (pin "25") (pinfunction "TXD0/GPIO16_25") (pintype "bidirectional"))
    )
    (net (code "50") (name "USB_D+") (class "Default")
      (node (ref "D1") (pin "4") (pinfunction "I/O2_2_4") (pintype "bidirectional"))
      (node (ref "U1") (pin "14") (pinfunction "IO13_14") (pintype "bidirectional"))
    )
    (net (code "51") (name "USB_D-") (class "Default")
      (node (ref "D1") (pin "6") (pinfunction "I/O1_2_6") (pintype "bidirectional"))
      (node (ref "U1") (pin "13") (pinfunction "IO12_13") (pintype "bidirectional"))
    )
    (net (code "52") (name "VBAT") (class "Default")
      (node (ref "C2_BAT") (pin "1") (pinfunction "1_1") (pintype "passive"))
      (node (ref "MCP73831") (pin "3") (pinfunction "VBAT_3") (pintype "power_in"))
      (node (ref "Q1") (pin "3") (pinfunction "D_3") (pintype "bidirectional"))
      (node (ref "TP3") (pin "TP") (pinfunction "TP_TP") (pintype "input"))
      (node (ref "U4") (pin "2") (pinfunction "CELL_2") (pintype "power_in"))
      (node (ref "U4") (pin "3") (pinfunction "VDD_3") (pintype "power_in"))
    )
    (net (code "53") (name "VBUS") (class "Default")
      (node (ref "C1_BAT") (pin "1") (pinfunction "1_1") (pintype "passive"))
      (node (ref "C4_USB") (pin "1") (pinfunction "1_1") (pintype "passive"))
      (node (ref "C5_USB") (pin "1") (pinfunction "1_1") (pintype "passive"))
      (node (ref "CHG_LED") (pin "A") (pinfunction "A_A") (pintype "passive"))
      (node (ref "D1") (pin "2") (pinfunction "GND_2") (pintype "bidirectional"))
      (node (ref "D2") (pin "2") (pinfunction "ANODE_2") (pintype "bidirectional"))
      (node (ref "MCP73831") (pin "4") (pinfunction "VIN_4") (pintype "power_in"))
      (node (ref "PFMF.050.1") (pin "2") (pinfunction "2_2") (pintype "passive"))
      (node (ref "Q1") (pin "1") (pinfunction "G_1") (pintype "bidirectional"))
      (node (ref "R1_PWRUSB") (pin "2") (pinfunction "2_2") (pintype "passive"))
      (node (ref "TP16") (pin "TP") (pinfunction "TP_TP") (pintype "input"))
    )
    (net (code "54") (name "VRTC") (class "Default")
      (node (ref "C1") (pin "1") (pinfunction "1_1") (pintype "passive"))
      (node (ref "C10_SUPERCAP") (pin "1") (pinfunction "1_1") (pintype "passive"))
      (node (ref "R_CAPACITOR") (pin "2") (pinfunction "2_2") (pintype "passive"))
      (node (ref "U3") (pin "14") (pinfunction "VBAT_14") (pintype "power_in"))
    )
    (net (code "55") (name "VUSB") (class "Default")
      (node (ref "J2") (pin "A4") (pinfunction "A4_A4") (pintype "bidirectional"))
      (node (ref "J2") (pin "A9") (pinfunction "A9_A9") (pintype "bidirectional"))
      (node (ref "J2") (pin "B4") (pinfunction "B4_B4") (pintype "bidirectional"))
      (node (ref "J2") (pin "B9") (pinfunction "B9_B9") (pintype "bidirectional"))
      (node (ref "PFMF.050.1") (pin "1") (pinfunction "1_1") (pintype "passive"))
    )
    (net (code "56") (name "unconnected-(IC1-NC-Pad4)") (class "Default")
      (node (ref "IC1") (pin "4") (pinfunction "NC_4") (pintype "no_connect"))
    )
    (net (code "57") (name "unconnected-(IC2-NC-Pad4)") (class "Default")
      (node (ref "IC2") (pin "4") (pinfunction "NC_4") (pintype "no_connect"))
    )
    (net (code "58") (name "unconnected-(J1-Pad1)") (class "Default")
      (node (ref "J1") (pin "1") (pinfunction "1_1") (pintype "bidirectional"))
    )
    (net (code "59") (name "unconnected-(J1-Pad6)") (class "Default")
      (node (ref "J1") (pin "6") (pinfunction "6_6") (pintype "bidirectional"))
    )
    (net (code "60") (name "unconnected-(J1-Pad7)") (class "Default")
      (node (ref "J1") (pin "7") (pinfunction "7_7") (pintype "bidirectional"))
    )
    (net (code "61") (name "unconnected-(J2-PadA8)") (class "Default")
      (node (ref "J2") (pin "A8") (pinfunction "A8_A8") (pintype "bidirectional"))
    )
    (net (code "62") (name "unconnected-(J2-PadB8)") (class "Default")
      (node (ref "J2") (pin "B8") (pinfunction "B8_B8") (pintype "bidirectional"))
    )
    (net (code "63") (name "unconnected-(J4-DAT1-PadP8)") (class "Default")
      (node (ref "J4") (pin "P8") (pinfunction "DAT1_P8") (pintype "bidirectional"))
    )
    (net (code "64") (name "unconnected-(J4-DAT2-PadP1)") (class "Default")
      (node (ref "J4") (pin "P1") (pinfunction "DAT2_P1") (pintype "bidirectional"))
    )
    (net (code "65") (name "unconnected-(J4-DETECTION_1-PadS1)") (class "Default")
      (node (ref "J4") (pin "S1") (pinfunction "DETECTION_1_S1") (pintype "bidirectional"))
    )
    (net (code "66") (name "unconnected-(J4-DETECTION_2-PadS2)") (class "Default")
      (node (ref "J4") (pin "S2") (pinfunction "DETECTION_2_S2") (pintype "bidirectional"))
    )
    (net (code "67") (name "unconnected-(U1-NC-Pad22)") (class "Default")
      (node (ref "U1") (pin "22") (pinfunction "NC_22") (pintype "no_connect"))
    )
    (net (code "68") (name "unconnected-(U4-~{ALERT}-Pad5)") (class "Default")
      (node (ref "U4") (pin "5") (pinfunction "~{ALERT}_5") (pintype "output"))
    )
  )
)
